# schematic-saved-reopened.net
KiCad netlist of a schematic drawn in EasyEDA
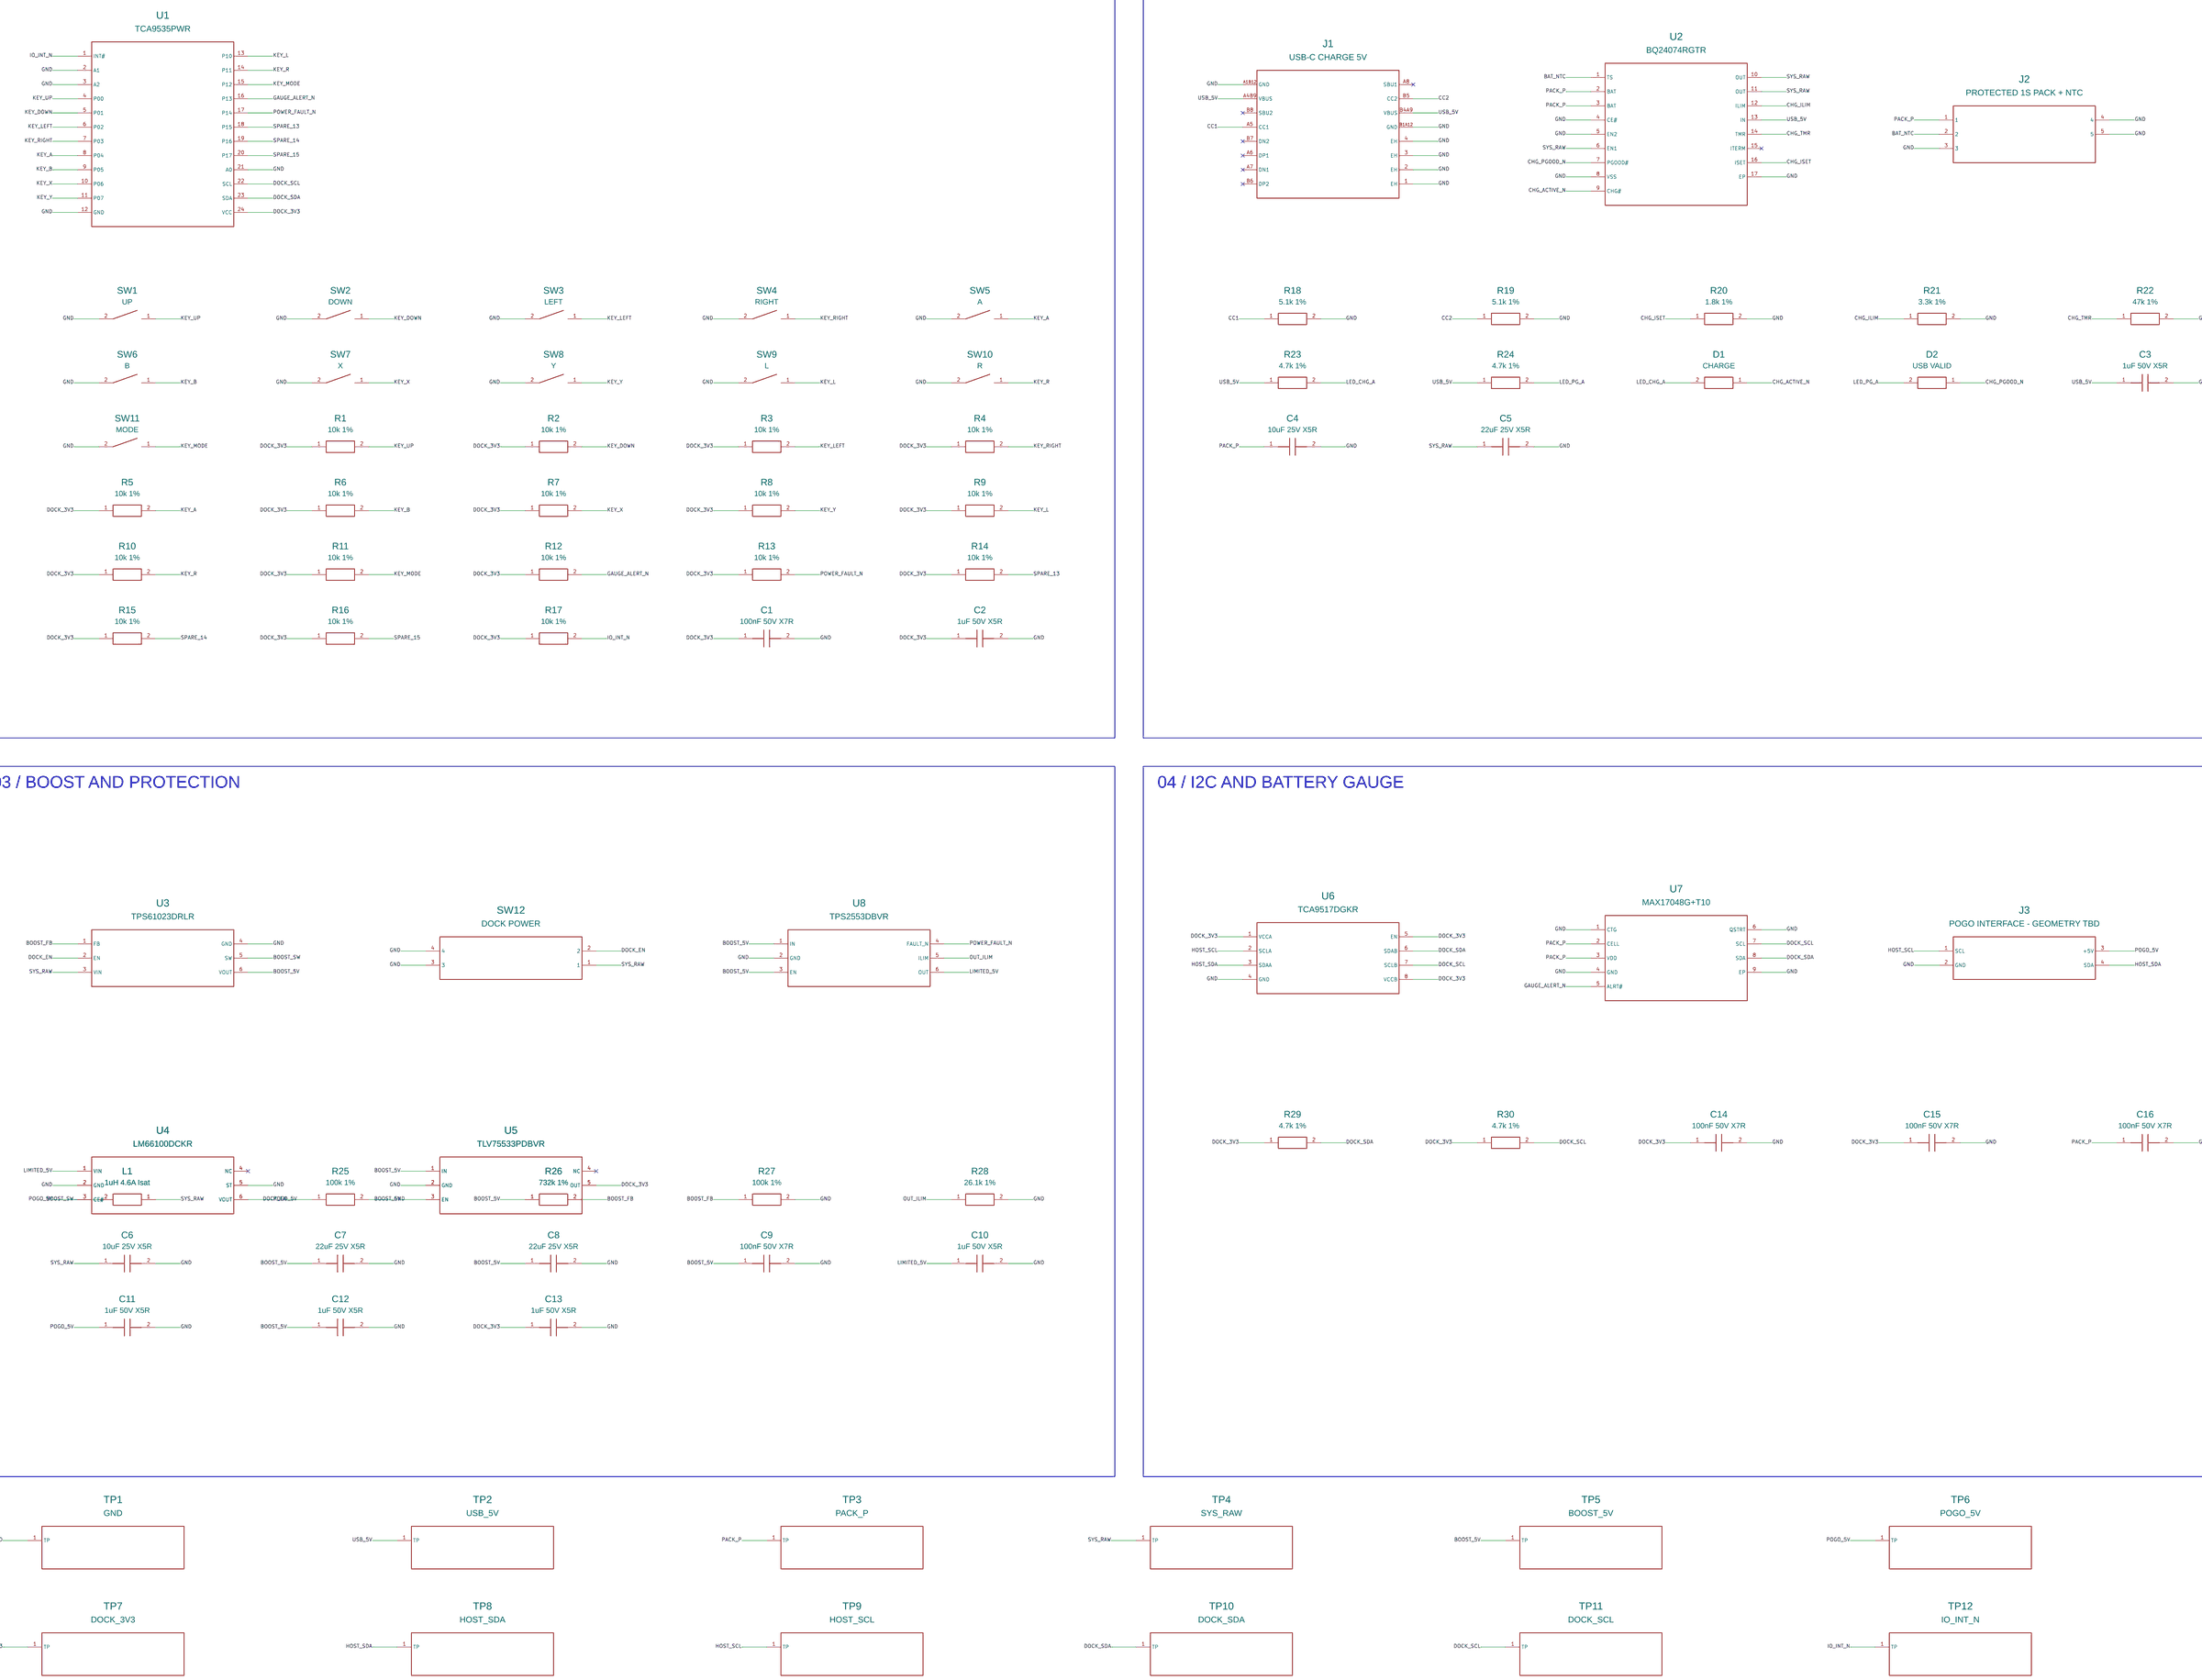
[diagram p0: schematic sheet]

(export (version "E")
  (design (tool "Eeschema 10.0.6"))
  (components
    (comp (ref "C1") (value "100nF 50V X7R") (libsource (lib "") (part "100nF 50V X7R")))
    (comp (ref "C2")
      (value "1uF 50V X5R")
      (fields
        (field (name "Manufacturer Part") "CL10A105KB8NNNC")
        (field (name "Manufacturer") "SAMSUNG(三星)")
      )
      (libsource (lib "") (part "1uF 50V X5R"))
    )
    (comp (ref "C3")
      (value "1uF 50V X5R")
      (fields
        (field (name "Manufacturer Part") "CL10A105KB8NNNC")
        (field (name "Manufacturer") "SAMSUNG(三星)")
      )
      (libsource (lib "") (part "1uF 50V X5R"))
    )
    (comp (ref "C4")
      (value "10uF 25V X5R")
      (fields
        (field (name "Manufacturer Part") "CL10A106MA8NRNC")
        (field (name "Manufacturer") "SAMSUNG(三星)")
      )
      (libsource (lib "") (part "10uF 25V X5R"))
    )
    (comp (ref "C5") (value "22uF 25V X5R") (libsource (lib "") (part "22uF 25V X5R")))
    (comp (ref "C6")
      (value "10uF 25V X5R")
      (fields
        (field (name "Manufacturer Part") "CL10A106MA8NRNC")
        (field (name "Manufacturer") "SAMSUNG(三星)")
      )
      (libsource (lib "") (part "10uF 25V X5R"))
    )
    (comp (ref "C7") (value "22uF 25V X5R") (libsource (lib "") (part "22uF 25V X5R")))
    (comp (ref "C8") (value "22uF 25V X5R") (libsource (lib "") (part "22uF 25V X5R")))
    (comp (ref "C9") (value "100nF 50V X7R") (libsource (lib "") (part "100nF 50V X7R")))
    (comp (ref "C10")
      (value "1uF 50V X5R")
      (fields
        (field (name "Manufacturer Part") "CL10A105KB8NNNC")
        (field (name "Manufacturer") "SAMSUNG(三星)")
      )
      (libsource (lib "") (part "1uF 50V X5R"))
    )
    (comp (ref "C11")
      (value "1uF 50V X5R")
      (fields
        (field (name "Manufacturer Part") "CL10A105KB8NNNC")
        (field (name "Manufacturer") "SAMSUNG(三星)")
      )
      (libsource (lib "") (part "1uF 50V X5R"))
    )
    (comp (ref "C12")
      (value "1uF 50V X5R")
      (fields
        (field (name "Manufacturer Part") "CL10A105KB8NNNC")
        (field (name "Manufacturer") "SAMSUNG(三星)")
      )
      (libsource (lib "") (part "1uF 50V X5R"))
    )
    (comp (ref "C13")
      (value "1uF 50V X5R")
      (fields
        (field (name "Manufacturer Part") "CL10A105KB8NNNC")
        (field (name "Manufacturer") "SAMSUNG(三星)")
      )
      (libsource (lib "") (part "1uF 50V X5R"))
    )
    (comp (ref "C14") (value "100nF 50V X7R") (libsource (lib "") (part "100nF 50V X7R")))
    (comp (ref "C15") (value "100nF 50V X7R") (libsource (lib "") (part "100nF 50V X7R")))
    (comp (ref "C16") (value "100nF 50V X7R") (libsource (lib "") (part "100nF 50V X7R")))
    (comp (ref "D1")
      (value "CHARGE")
      (fields (field (name "Manufacturer Part") "KT-0805黄灯") (field (name "Manufacturer") "KENTO"))
      (libsource (lib "") (part "CHARGE"))
    )
    (comp (ref "D2")
      (value "USB VALID")
      (fields (field (name "Manufacturer Part") "KT-0805黄灯") (field (name "Manufacturer") "KENTO"))
      (libsource (lib "") (part "USB VALID"))
    )
    (comp (ref "J1")
      (value "USB-C CHARGE 5V")
      (fields (field (name "Manufacturer Part") "TYPE-C-31-M-12") (field (name "Manufacturer") "韩国韩荣"))
      (libsource (lib "") (part "USB-C CHARGE 5V"))
    )
    (comp (ref "J2")
      (value "PROTECTED 1S PACK + NTC")
      (fields (field (name "Manufacturer Part") "B3B-PH-SM4-TB(LF)(SN)") (field (name "Manufacturer") "JST"))
      (libsource (lib "") (part "PROTECTED 1S PACK + NTC"))
    )
    (comp (ref "J3")
      (value "POGO INTERFACE - GEOMETRY TBD")
      (libsource (lib "") (part "POGO INTERFACE - GEOMETRY TBD"))
    )
    (comp (ref "L1")
      (value "1uH 4.6A Isat")
      (fields
        (field (name "Manufacturer Part") "FTC201610S1R0MBCA")
        (field (name "Manufacturer") "cjiang(长江微电)")
      )
      (libsource (lib "") (part "1uH 4.6A Isat"))
    )
    (comp (ref "R1")
      (value "10k 1%")
      (fields
        (field (name "Manufacturer Part") "0603WAF1002T5E")
        (field (name "Manufacturer") "UNI-ROYAL(厚声)")
      )
      (libsource (lib "") (part "10k 1%"))
    )
    (comp (ref "R2")
      (value "10k 1%")
      (fields
        (field (name "Manufacturer Part") "0603WAF1002T5E")
        (field (name "Manufacturer") "UNI-ROYAL(厚声)")
      )
      (libsource (lib "") (part "10k 1%"))
    )
    (comp (ref "R3")
      (value "10k 1%")
      (fields
        (field (name "Manufacturer Part") "0603WAF1002T5E")
        (field (name "Manufacturer") "UNI-ROYAL(厚声)")
      )
      (libsource (lib "") (part "10k 1%"))
    )
    (comp (ref "R4")
      (value "10k 1%")
      (fields
        (field (name "Manufacturer Part") "0603WAF1002T5E")
        (field (name "Manufacturer") "UNI-ROYAL(厚声)")
      )
      (libsource (lib "") (part "10k 1%"))
    )
    (comp (ref "R5")
      (value "10k 1%")
      (fields
        (field (name "Manufacturer Part") "0603WAF1002T5E")
        (field (name "Manufacturer") "UNI-ROYAL(厚声)")
      )
      (libsource (lib "") (part "10k 1%"))
    )
    (comp (ref "R6")
      (value "10k 1%")
      (fields
        (field (name "Manufacturer Part") "0603WAF1002T5E")
        (field (name "Manufacturer") "UNI-ROYAL(厚声)")
      )
      (libsource (lib "") (part "10k 1%"))
    )
    (comp (ref "R7")
      (value "10k 1%")
      (fields
        (field (name "Manufacturer Part") "0603WAF1002T5E")
        (field (name "Manufacturer") "UNI-ROYAL(厚声)")
      )
      (libsource (lib "") (part "10k 1%"))
    )
    (comp (ref "R8")
      (value "10k 1%")
      (fields
        (field (name "Manufacturer Part") "0603WAF1002T5E")
        (field (name "Manufacturer") "UNI-ROYAL(厚声)")
      )
      (libsource (lib "") (part "10k 1%"))
    )
    (comp (ref "R9")
      (value "10k 1%")
      (fields
        (field (name "Manufacturer Part") "0603WAF1002T5E")
        (field (name "Manufacturer") "UNI-ROYAL(厚声)")
      )
      (libsource (lib "") (part "10k 1%"))
    )
    (comp (ref "R10")
      (value "10k 1%")
      (fields
        (field (name "Manufacturer Part") "0603WAF1002T5E")
        (field (name "Manufacturer") "UNI-ROYAL(厚声)")
      )
      (libsource (lib "") (part "10k 1%"))
    )
    (comp (ref "R11")
      (value "10k 1%")
      (fields
        (field (name "Manufacturer Part") "0603WAF1002T5E")
        (field (name "Manufacturer") "UNI-ROYAL(厚声)")
      )
      (libsource (lib "") (part "10k 1%"))
    )
    (comp (ref "R12")
      (value "10k 1%")
      (fields
        (field (name "Manufacturer Part") "0603WAF1002T5E")
        (field (name "Manufacturer") "UNI-ROYAL(厚声)")
      )
      (libsource (lib "") (part "10k 1%"))
    )
    (comp (ref "R13")
      (value "10k 1%")
      (fields
        (field (name "Manufacturer Part") "0603WAF1002T5E")
        (field (name "Manufacturer") "UNI-ROYAL(厚声)")
      )
      (libsource (lib "") (part "10k 1%"))
    )
    (comp (ref "R14")
      (value "10k 1%")
      (fields
        (field (name "Manufacturer Part") "0603WAF1002T5E")
        (field (name "Manufacturer") "UNI-ROYAL(厚声)")
      )
      (libsource (lib "") (part "10k 1%"))
    )
    (comp (ref "R15")
      (value "10k 1%")
      (fields
        (field (name "Manufacturer Part") "0603WAF1002T5E")
        (field (name "Manufacturer") "UNI-ROYAL(厚声)")
      )
      (libsource (lib "") (part "10k 1%"))
    )
    (comp (ref "R16")
      (value "10k 1%")
      (fields
        (field (name "Manufacturer Part") "0603WAF1002T5E")
        (field (name "Manufacturer") "UNI-ROYAL(厚声)")
      )
      (libsource (lib "") (part "10k 1%"))
    )
    (comp (ref "R17")
      (value "10k 1%")
      (fields
        (field (name "Manufacturer Part") "0603WAF1002T5E")
        (field (name "Manufacturer") "UNI-ROYAL(厚声)")
      )
      (libsource (lib "") (part "10k 1%"))
    )
    (comp (ref "R18")
      (value "5.1k 1%")
      (fields
        (field (name "Manufacturer Part") "0603WAF5101T5E")
        (field (name "Manufacturer") "UNI-ROYAL(厚声)")
      )
      (libsource (lib "") (part "5.1k 1%"))
    )
    (comp (ref "R19")
      (value "5.1k 1%")
      (fields
        (field (name "Manufacturer Part") "0603WAF5101T5E")
        (field (name "Manufacturer") "UNI-ROYAL(厚声)")
      )
      (libsource (lib "") (part "5.1k 1%"))
    )
    (comp (ref "R20") (value "1.8k 1%") (libsource (lib "") (part "1.8k 1%")))
    (comp (ref "R21") (value "3.3k 1%") (libsource (lib "") (part "3.3k 1%")))
    (comp (ref "R22") (value "47k 1%") (libsource (lib "") (part "47k 1%")))
    (comp (ref "R23")
      (value "4.7k 1%")
      (fields
        (field (name "Manufacturer Part") "0603WAF4701T5E")
        (field (name "Manufacturer") "UNI-ROYAL(厚声)")
      )
      (libsource (lib "") (part "4.7k 1%"))
    )
    (comp (ref "R24")
      (value "4.7k 1%")
      (fields
        (field (name "Manufacturer Part") "0603WAF4701T5E")
        (field (name "Manufacturer") "UNI-ROYAL(厚声)")
      )
      (libsource (lib "") (part "4.7k 1%"))
    )
    (comp (ref "R25")
      (value "100k 1%")
      (fields
        (field (name "Manufacturer Part") "0603WAF1003T5E")
        (field (name "Manufacturer") "UNI-ROYAL(厚声)")
      )
      (libsource (lib "") (part "100k 1%"))
    )
    (comp (ref "R26") (value "732k 1%") (libsource (lib "") (part "732k 1%")))
    (comp (ref "R27")
      (value "100k 1%")
      (fields
        (field (name "Manufacturer Part") "0603WAF1003T5E")
        (field (name "Manufacturer") "UNI-ROYAL(厚声)")
      )
      (libsource (lib "") (part "100k 1%"))
    )
    (comp (ref "R28") (value "26.1k 1%") (libsource (lib "") (part "26.1k 1%")))
    (comp (ref "R29")
      (value "4.7k 1%")
      (fields
        (field (name "Manufacturer Part") "0603WAF4701T5E")
        (field (name "Manufacturer") "UNI-ROYAL(厚声)")
      )
      (libsource (lib "") (part "4.7k 1%"))
    )
    (comp (ref "R30")
      (value "4.7k 1%")
      (fields
        (field (name "Manufacturer Part") "0603WAF4701T5E")
        (field (name "Manufacturer") "UNI-ROYAL(厚声)")
      )
      (libsource (lib "") (part "4.7k 1%"))
    )
    (comp (ref "SW1")
      (value "UP")
      (fields (field (name "Manufacturer Part") "TS-1088-AR02016") (field (name "Manufacturer") "XUNPU(讯普)"))
      (libsource (lib "") (part "UP"))
    )
    (comp (ref "SW2")
      (value "DOWN")
      (fields (field (name "Manufacturer Part") "TS-1088-AR02016") (field (name "Manufacturer") "XUNPU(讯普)"))
      (libsource (lib "") (part "DOWN"))
    )
    (comp (ref "SW3")
      (value "LEFT")
      (fields (field (name "Manufacturer Part") "TS-1088-AR02016") (field (name "Manufacturer") "XUNPU(讯普)"))
      (libsource (lib "") (part "LEFT"))
    )
    (comp (ref "SW4")
      (value "RIGHT")
      (fields (field (name "Manufacturer Part") "TS-1088-AR02016") (field (name "Manufacturer") "XUNPU(讯普)"))
      (libsource (lib "") (part "RIGHT"))
    )
    (comp (ref "SW5")
      (value "A")
      (fields (field (name "Manufacturer Part") "TS-1088-AR02016") (field (name "Manufacturer") "XUNPU(讯普)"))
      (libsource (lib "") (part "A"))
    )
    (comp (ref "SW6")
      (value "B")
      (fields (field (name "Manufacturer Part") "TS-1088-AR02016") (field (name "Manufacturer") "XUNPU(讯普)"))
      (libsource (lib "") (part "B"))
    )
    (comp (ref "SW7")
      (value "X")
      (fields (field (name "Manufacturer Part") "TS-1088-AR02016") (field (name "Manufacturer") "XUNPU(讯普)"))
      (libsource (lib "") (part "X"))
    )
    (comp (ref "SW8")
      (value "Y")
      (fields (field (name "Manufacturer Part") "TS-1088-AR02016") (field (name "Manufacturer") "XUNPU(讯普)"))
      (libsource (lib "") (part "Y"))
    )
    (comp (ref "SW9")
      (value "L")
      (fields (field (name "Manufacturer Part") "TS-1088-AR02016") (field (name "Manufacturer") "XUNPU(讯普)"))
      (libsource (lib "") (part "L"))
    )
    (comp (ref "SW10")
      (value "R")
      (fields (field (name "Manufacturer Part") "TS-1088-AR02016") (field (name "Manufacturer") "XUNPU(讯普)"))
      (libsource (lib "") (part "R"))
    )
    (comp (ref "SW11")
      (value "MODE")
      (fields (field (name "Manufacturer Part") "TS-1088-AR02016") (field (name "Manufacturer") "XUNPU(讯普)"))
      (libsource (lib "") (part "MODE"))
    )
    (comp (ref "SW12")
      (value "DOCK POWER")
      (fields (field (name "Manufacturer Part") "MSK12C02") (field (name "Manufacturer") "SHOU HAN(首韩)"))
      (libsource (lib "") (part "DOCK POWER"))
    )
    (comp (ref "TP1") (value "GND") (libsource (lib "") (part "GND")))
    (comp (ref "TP2") (value "USB_5V") (libsource (lib "") (part "USB_5V")))
    (comp (ref "TP3") (value "PACK_P") (libsource (lib "") (part "PACK_P")))
    (comp (ref "TP4") (value "SYS_RAW") (libsource (lib "") (part "SYS_RAW")))
    (comp (ref "TP5") (value "BOOST_5V") (libsource (lib "") (part "BOOST_5V")))
    (comp (ref "TP6") (value "POGO_5V") (libsource (lib "") (part "POGO_5V")))
    (comp (ref "TP7") (value "DOCK_3V3") (libsource (lib "") (part "DOCK_3V3")))
    (comp (ref "TP8") (value "HOST_SDA") (libsource (lib "") (part "HOST_SDA")))
    (comp (ref "TP9") (value "HOST_SCL") (libsource (lib "") (part "HOST_SCL")))
    (comp (ref "TP10") (value "DOCK_SDA") (libsource (lib "") (part "DOCK_SDA")))
    (comp (ref "TP11") (value "DOCK_SCL") (libsource (lib "") (part "DOCK_SCL")))
    (comp (ref "TP12") (value "IO_INT_N") (libsource (lib "") (part "IO_INT_N")))
    (comp (ref "U1")
      (value "TCA9535PWR")
      (fields (field (name "Manufacturer") "TI(德州仪器)"))
      (libsource (lib "") (part "TCA9535PWR"))
    )
    (comp (ref "U2")
      (value "BQ24074RGTR")
      (fields (field (name "Manufacturer") "TI(德州仪器)"))
      (libsource (lib "") (part "BQ24074RGTR"))
    )
    (comp (ref "U3")
      (value "TPS61023DRLR")
      (fields (field (name "Manufacturer") "TI(德州仪器)"))
      (libsource (lib "") (part "TPS61023DRLR"))
    )
    (comp (ref "U4")
      (value "LM66100DCKR")
      (fields (field (name "Manufacturer") "TI(德州仪器)"))
      (libsource (lib "") (part "LM66100DCKR"))
    )
    (comp (ref "U5")
      (value "TLV75533PDBVR")
      (fields (field (name "Manufacturer") "TI(德州仪器)"))
      (libsource (lib "") (part "TLV75533PDBVR"))
    )
    (comp (ref "U6")
      (value "TCA9517DGKR")
      (fields (field (name "Manufacturer") "TI(德州仪器)"))
      (libsource (lib "") (part "TCA9517DGKR"))
    )
    (comp (ref "U7")
      (value "MAX17048G+T10")
      (fields (field (name "Manufacturer") "ADI(亚德诺)/MAXIM(美信)"))
      (libsource (lib "") (part "MAX17048G+T10"))
    )
    (comp (ref "U8") (value "TPS2553DBVR") (libsource (lib "") (part "TPS2553DBVR")))
  )
  (nets
    (net (code "1") (name "/BAT_NTC") (class "Default")
      (node (ref "J2") (pin "2") (pinfunction "2_2") (pintype "unspecified"))
      (node (ref "U2") (pin "1") (pinfunction "TS_1") (pintype "unspecified"))
    )
    (net (code "2") (name "/BOOST_5V") (class "Default")
      (node (ref "C12") (pin "1") (pintype "unspecified"))
      (node (ref "C7") (pin "1") (pintype "unspecified"))
      (node (ref "C8") (pin "1") (pintype "unspecified"))
      (node (ref "C9") (pin "1") (pintype "unspecified"))
      (node (ref "R26") (pin "1") (pintype "unspecified"))
      (node (ref "TP5") (pin "1") (pinfunction "TP_1") (pintype "unspecified"))
      (node (ref "U3") (pin "6") (pinfunction "VOUT_6") (pintype "unspecified"))
      (node (ref "U5") (pin "1") (pinfunction "IN_1") (pintype "unspecified"))
      (node (ref "U5") (pin "3") (pinfunction "EN_3") (pintype "unspecified"))
      (node (ref "U8") (pin "1") (pinfunction "IN_1") (pintype "unspecified"))
      (node (ref "U8") (pin "3") (pinfunction "EN_3") (pintype "unspecified"))
    )
    (net (code "3") (name "/BOOST_FB") (class "Default")
      (node (ref "R26") (pin "2") (pintype "unspecified"))
      (node (ref "R27") (pin "1") (pintype "unspecified"))
      (node (ref "U3") (pin "1") (pinfunction "FB_1") (pintype "unspecified"))
    )
    (net (code "4") (name "/BOOST_SW") (class "Default")
      (node (ref "C11") (pin "1") (pintype "unspecified"))
      (node (ref "J3") (pin "3") (pinfunction "+5V_3") (pintype "unspecified"))
      (node (ref "L1") (pin "2") (pintype "unspecified"))
      (node (ref "TP6") (pin "1") (pinfunction "TP_1") (pintype "unspecified"))
      (node (ref "U3") (pin "5") (pinfunction "SW_5") (pintype "unspecified"))
      (node (ref "U4") (pin "3") (pinfunction "CE#_3") (pintype "unspecified"))
      (node (ref "U4") (pin "6") (pinfunction "VOUT_6") (pintype "unspecified"))
    )
    (net (code "5") (name "/CC1") (class "Default")
      (node (ref "J1") (pin "A5") (pinfunction "CC1_A5") (pintype "unspecified"))
      (node (ref "R18") (pin "1") (pintype "unspecified"))
    )
    (net (code "6") (name "/CC2") (class "Default")
      (node (ref "J1") (pin "B5") (pinfunction "CC2_B5") (pintype "unspecified"))
      (node (ref "R19") (pin "1") (pintype "unspecified"))
    )
    (net (code "7") (name "/CHG_ACTIVE_N") (class "Default")
      (node (ref "D1") (pin "1") (pintype "unspecified"))
      (node (ref "U2") (pin "9") (pinfunction "CHG#_9") (pintype "unspecified"))
    )
    (net (code "8") (name "/CHG_ILIM") (class "Default")
      (node (ref "R21") (pin "1") (pintype "unspecified"))
      (node (ref "U2") (pin "12") (pinfunction "ILIM_12") (pintype "unspecified"))
    )
    (net (code "9") (name "/CHG_ISET") (class "Default")
      (node (ref "R20") (pin "1") (pintype "unspecified"))
      (node (ref "U2") (pin "16") (pinfunction "ISET_16") (pintype "unspecified"))
    )
    (net (code "10") (name "/CHG_PGOOD_N") (class "Default")
      (node (ref "D2") (pin "1") (pintype "unspecified"))
      (node (ref "U2") (pin "7") (pinfunction "PGOOD#_7") (pintype "unspecified"))
    )
    (net (code "11") (name "/CHG_TMR") (class "Default")
      (node (ref "R22") (pin "1") (pintype "unspecified"))
      (node (ref "U2") (pin "14") (pinfunction "TMR_14") (pintype "unspecified"))
    )
    (net (code "12") (name "/DOCK_3V3") (class "Default")
      (node (ref "C1") (pin "1") (pintype "unspecified"))
      (node (ref "C13") (pin "1") (pintype "unspecified"))
      (node (ref "C14") (pin "1") (pintype "unspecified"))
      (node (ref "C15") (pin "1") (pintype "unspecified"))
      (node (ref "C2") (pin "1") (pintype "unspecified"))
      (node (ref "R1") (pin "1") (pintype "unspecified"))
      (node (ref "R10") (pin "1") (pintype "unspecified"))
      (node (ref "R11") (pin "1") (pintype "unspecified"))
      (node (ref "R12") (pin "1") (pintype "unspecified"))
      (node (ref "R13") (pin "1") (pintype "unspecified"))
      (node (ref "R14") (pin "1") (pintype "unspecified"))
      (node (ref "R15") (pin "1") (pintype "unspecified"))
      (node (ref "R16") (pin "1") (pintype "unspecified"))
      (node (ref "R17") (pin "1") (pintype "unspecified"))
      (node (ref "R2") (pin "1") (pintype "unspecified"))
      (node (ref "R29") (pin "1") (pintype "unspecified"))
      (node (ref "R3") (pin "1") (pintype "unspecified"))
      (node (ref "R30") (pin "1") (pintype "unspecified"))
      (node (ref "R4") (pin "1") (pintype "unspecified"))
      (node (ref "R5") (pin "1") (pintype "unspecified"))
      (node (ref "R6") (pin "1") (pintype "unspecified"))
      (node (ref "R7") (pin "1") (pintype "unspecified"))
      (node (ref "R8") (pin "1") (pintype "unspecified"))
      (node (ref "R9") (pin "1") (pintype "unspecified"))
      (node (ref "TP7") (pin "1") (pinfunction "TP_1") (pintype "unspecified"))
      (node (ref "U1") (pin "24") (pinfunction "VCC_24") (pintype "unspecified"))
      (node (ref "U5") (pin "5") (pinfunction "OUT_5") (pintype "unspecified"))
      (node (ref "U6") (pin "1") (pinfunction "VCCA_1") (pintype "unspecified"))
      (node (ref "U6") (pin "5") (pinfunction "EN_5") (pintype "unspecified"))
      (node (ref "U6") (pin "8") (pinfunction "VCCB_8") (pintype "unspecified"))
    )
    (net (code "13") (name "/DOCK_EN") (class "Default")
      (node (ref "R25") (pin "1") (pintype "unspecified"))
      (node (ref "SW12") (pin "2") (pinfunction "2_2") (pintype "unspecified"))
      (node (ref "U3") (pin "2") (pinfunction "EN_2") (pintype "unspecified"))
    )
    (net (code "14") (name "/DOCK_SCL") (class "Default")
      (node (ref "R30") (pin "2") (pintype "unspecified"))
      (node (ref "TP11") (pin "1") (pinfunction "TP_1") (pintype "unspecified"))
      (node (ref "U1") (pin "22") (pinfunction "SCL_22") (pintype "unspecified"))
      (node (ref "U6") (pin "7") (pinfunction "SCLB_7") (pintype "unspecified"))
      (node (ref "U7") (pin "7") (pinfunction "SCL_7") (pintype "unspecified"))
    )
    (net (code "15") (name "/DOCK_SDA") (class "Default")
      (node (ref "R29") (pin "2") (pintype "unspecified"))
      (node (ref "TP10") (pin "1") (pinfunction "TP_1") (pintype "unspecified"))
      (node (ref "U1") (pin "23") (pinfunction "SDA_23") (pintype "unspecified"))
      (node (ref "U6") (pin "6") (pinfunction "SDAB_6") (pintype "unspecified"))
      (node (ref "U7") (pin "8") (pinfunction "SDA_8") (pintype "unspecified"))
    )
    (net (code "16") (name "/GAUGE_ALERT_N") (class "Default")
      (node (ref "R12") (pin "2") (pintype "unspecified"))
      (node (ref "U1") (pin "16") (pinfunction "P13_16") (pintype "unspecified"))
      (node (ref "U7") (pin "5") (pinfunction "ALRT#_5") (pintype "unspecified"))
    )
    (net (code "17") (name "/GND") (class "Default")
      (node (ref "C1") (pin "2") (pintype "unspecified"))
      (node (ref "C10") (pin "2") (pintype "unspecified"))
      (node (ref "C11") (pin "2") (pintype "unspecified"))
      (node (ref "C12") (pin "2") (pintype "unspecified"))
      (node (ref "C13") (pin "2") (pintype "unspecified"))
      (node (ref "C14") (pin "2") (pintype "unspecified"))
      (node (ref "C15") (pin "2") (pintype "unspecified"))
      (node (ref "C16") (pin "2") (pintype "unspecified"))
      (node (ref "C2") (pin "2") (pintype "unspecified"))
      (node (ref "C3") (pin "2") (pintype "unspecified"))
      (node (ref "C4") (pin "2") (pintype "unspecified"))
      (node (ref "C5") (pin "2") (pintype "unspecified"))
      (node (ref "C6") (pin "2") (pintype "unspecified"))
      (node (ref "C7") (pin "2") (pintype "unspecified"))
      (node (ref "C8") (pin "2") (pintype "unspecified"))
      (node (ref "C9") (pin "2") (pintype "unspecified"))
      (node (ref "J1") (pin "1") (pinfunction "EH_1") (pintype "unspecified"))
      (node (ref "J1") (pin "2") (pinfunction "EH_2") (pintype "unspecified"))
      (node (ref "J1") (pin "3") (pinfunction "EH_3") (pintype "unspecified"))
      (node (ref "J1") (pin "4") (pinfunction "EH_4") (pintype "unspecified"))
      (node (ref "J1") (pin "A1B12") (pinfunction "GND_A1B12") (pintype "unspecified"))
      (node (ref "J1") (pin "B1A12") (pinfunction "GND_B1A12") (pintype "unspecified"))
      (node (ref "J2") (pin "3") (pinfunction "3_3") (pintype "unspecified"))
      (node (ref "J2") (pin "4") (pinfunction "4_4") (pintype "unspecified"))
      (node (ref "J2") (pin "5") (pinfunction "5_5") (pintype "unspecified"))
      (node (ref "J3") (pin "2") (pinfunction "GND_2") (pintype "unspecified"))
      (node (ref "R18") (pin "2") (pintype "unspecified"))
      (node (ref "R19") (pin "2") (pintype "unspecified"))
      (node (ref "R20") (pin "2") (pintype "unspecified"))
      (node (ref "R21") (pin "2") (pintype "unspecified"))
      (node (ref "R22") (pin "2") (pintype "unspecified"))
      (node (ref "R25") (pin "2") (pintype "unspecified"))
      (node (ref "R27") (pin "2") (pintype "unspecified"))
      (node (ref "R28") (pin "2") (pintype "unspecified"))
      (node (ref "SW1") (pin "2") (pintype "unspecified"))
      (node (ref "SW10") (pin "2") (pintype "unspecified"))
      (node (ref "SW11") (pin "2") (pintype "unspecified"))
      (node (ref "SW12") (pin "3") (pinfunction "3_3") (pintype "unspecified"))
      (node (ref "SW12") (pin "4") (pinfunction "4_4") (pintype "unspecified"))
      (node (ref "SW2") (pin "2") (pintype "unspecified"))
      (node (ref "SW3") (pin "2") (pintype "unspecified"))
      (node (ref "SW4") (pin "2") (pintype "unspecified"))
      (node (ref "SW5") (pin "2") (pintype "unspecified"))
      (node (ref "SW6") (pin "2") (pintype "unspecified"))
      (node (ref "SW7") (pin "2") (pintype "unspecified"))
      (node (ref "SW8") (pin "2") (pintype "unspecified"))
      (node (ref "SW9") (pin "2") (pintype "unspecified"))
      (node (ref "TP1") (pin "1") (pinfunction "TP_1") (pintype "unspecified"))
      (node (ref "U1") (pin "12") (pinfunction "GND_12") (pintype "unspecified"))
      (node (ref "U1") (pin "2") (pinfunction "A1_2") (pintype "unspecified"))
      (node (ref "U1") (pin "21") (pinfunction "A0_21") (pintype "unspecified"))
      (node (ref "U1") (pin "3") (pinfunction "A2_3") (pintype "unspecified"))
      (node (ref "U2") (pin "17") (pinfunction "EP_17") (pintype "unspecified"))
      (node (ref "U2") (pin "4") (pinfunction "CE#_4") (pintype "unspecified"))
      (node (ref "U2") (pin "5") (pinfunction "EN2_5") (pintype "unspecified"))
      (node (ref "U2") (pin "8") (pinfunction "VSS_8") (pintype "unspecified"))
      (node (ref "U3") (pin "4") (pinfunction "GND_4") (pintype "unspecified"))
      (node (ref "U4") (pin "2") (pinfunction "GND_2") (pintype "unspecified"))
      (node (ref "U4") (pin "5") (pinfunction "ST_5") (pintype "unspecified"))
      (node (ref "U5") (pin "2") (pinfunction "GND_2") (pintype "unspecified"))
      (node (ref "U6") (pin "4") (pinfunction "GND_4") (pintype "unspecified"))
      (node (ref "U7") (pin "1") (pinfunction "CTG_1") (pintype "unspecified"))
      (node (ref "U7") (pin "4") (pinfunction "GND_4") (pintype "unspecified"))
      (node (ref "U7") (pin "6") (pinfunction "QSTRT_6") (pintype "unspecified"))
      (node (ref "U7") (pin "9") (pinfunction "EP_9") (pintype "unspecified"))
      (node (ref "U8") (pin "2") (pinfunction "GND_2") (pintype "unspecified"))
    )
    (net (code "18") (name "/HOST_SCL") (class "Default")
      (node (ref "J3") (pin "1") (pinfunction "SCL_1") (pintype "unspecified"))
      (node (ref "TP9") (pin "1") (pinfunction "TP_1") (pintype "unspecified"))
      (node (ref "U6") (pin "2") (pinfunction "SCLA_2") (pintype "unspecified"))
    )
    (net (code "19") (name "/HOST_SDA") (class "Default")
      (node (ref "J3") (pin "4") (pinfunction "SDA_4") (pintype "unspecified"))
      (node (ref "TP8") (pin "1") (pinfunction "TP_1") (pintype "unspecified"))
      (node (ref "U6") (pin "3") (pinfunction "SDAA_3") (pintype "unspecified"))
    )
    (net (code "20") (name "/IO_INT_N") (class "Default")
      (node (ref "R17") (pin "2") (pintype "unspecified"))
      (node (ref "TP12") (pin "1") (pinfunction "TP_1") (pintype "unspecified"))
      (node (ref "U1") (pin "1") (pinfunction "INT#_1") (pintype "unspecified"))
    )
    (net (code "21") (name "/KEY_A") (class "Default")
      (node (ref "R5") (pin "2") (pintype "unspecified"))
      (node (ref "SW5") (pin "1") (pintype "unspecified"))
      (node (ref "U1") (pin "8") (pinfunction "P04_8") (pintype "unspecified"))
    )
    (net (code "22") (name "/KEY_B") (class "Default")
      (node (ref "R6") (pin "2") (pintype "unspecified"))
      (node (ref "SW6") (pin "1") (pintype "unspecified"))
      (node (ref "U1") (pin "9") (pinfunction "P05_9") (pintype "unspecified"))
    )
    (net (code "23") (name "/KEY_DOWN") (class "Default")
      (node (ref "R2") (pin "2") (pintype "unspecified"))
      (node (ref "SW2") (pin "1") (pintype "unspecified"))
      (node (ref "U1") (pin "5") (pinfunction "P01_5") (pintype "unspecified"))
    )
    (net (code "24") (name "/KEY_L") (class "Default")
      (node (ref "R9") (pin "2") (pintype "unspecified"))
      (node (ref "SW9") (pin "1") (pintype "unspecified"))
      (node (ref "U1") (pin "13") (pinfunction "P10_13") (pintype "unspecified"))
    )
    (net (code "25") (name "/KEY_LEFT") (class "Default")
      (node (ref "R3") (pin "2") (pintype "unspecified"))
      (node (ref "SW3") (pin "1") (pintype "unspecified"))
      (node (ref "U1") (pin "6") (pinfunction "P02_6") (pintype "unspecified"))
    )
    (net (code "26") (name "/KEY_MODE") (class "Default")
      (node (ref "R11") (pin "2") (pintype "unspecified"))
      (node (ref "SW11") (pin "1") (pintype "unspecified"))
      (node (ref "U1") (pin "15") (pinfunction "P12_15") (pintype "unspecified"))
    )
    (net (code "27") (name "/KEY_R") (class "Default")
      (node (ref "R10") (pin "2") (pintype "unspecified"))
      (node (ref "SW10") (pin "1") (pintype "unspecified"))
      (node (ref "U1") (pin "14") (pinfunction "P11_14") (pintype "unspecified"))
    )
    (net (code "28") (name "/KEY_RIGHT") (class "Default")
      (node (ref "R4") (pin "2") (pintype "unspecified"))
      (node (ref "SW4") (pin "1") (pintype "unspecified"))
      (node (ref "U1") (pin "7") (pinfunction "P03_7") (pintype "unspecified"))
    )
    (net (code "29") (name "/KEY_UP") (class "Default")
      (node (ref "R1") (pin "2") (pintype "unspecified"))
      (node (ref "SW1") (pin "1") (pintype "unspecified"))
      (node (ref "U1") (pin "4") (pinfunction "P00_4") (pintype "unspecified"))
    )
    (net (code "30") (name "/KEY_X") (class "Default")
      (node (ref "R7") (pin "2") (pintype "unspecified"))
      (node (ref "SW7") (pin "1") (pintype "unspecified"))
      (node (ref "U1") (pin "10") (pinfunction "P06_10") (pintype "unspecified"))
    )
    (net (code "31") (name "/KEY_Y") (class "Default")
      (node (ref "R8") (pin "2") (pintype "unspecified"))
      (node (ref "SW8") (pin "1") (pintype "unspecified"))
      (node (ref "U1") (pin "11") (pinfunction "P07_11") (pintype "unspecified"))
    )
    (net (code "32") (name "/LED_CHG_A") (class "Default")
      (node (ref "D1") (pin "2") (pintype "unspecified"))
      (node (ref "R23") (pin "2") (pintype "unspecified"))
    )
    (net (code "33") (name "/LED_PG_A") (class "Default")
      (node (ref "D2") (pin "2") (pintype "unspecified"))
      (node (ref "R24") (pin "2") (pintype "unspecified"))
    )
    (net (code "34") (name "/LIMITED_5V") (class "Default")
      (node (ref "C10") (pin "1") (pintype "unspecified"))
      (node (ref "U4") (pin "1") (pinfunction "VIN_1") (pintype "unspecified"))
      (node (ref "U8") (pin "6") (pinfunction "OUT_6") (pintype "unspecified"))
    )
    (net (code "35") (name "/OUT_ILIM") (class "Default")
      (node (ref "R28") (pin "1") (pintype "unspecified"))
      (node (ref "U8") (pin "5") (pinfunction "ILIM_5") (pintype "unspecified"))
    )
    (net (code "36") (name "/PACK_P") (class "Default")
      (node (ref "C16") (pin "1") (pintype "unspecified"))
      (node (ref "C4") (pin "1") (pintype "unspecified"))
      (node (ref "J2") (pin "1") (pinfunction "1_1") (pintype "unspecified"))
      (node (ref "TP3") (pin "1") (pinfunction "TP_1") (pintype "unspecified"))
      (node (ref "U2") (pin "2") (pinfunction "BAT_2") (pintype "unspecified"))
      (node (ref "U2") (pin "3") (pinfunction "BAT_3") (pintype "unspecified"))
      (node (ref "U7") (pin "2") (pinfunction "CELL_2") (pintype "unspecified"))
      (node (ref "U7") (pin "3") (pinfunction "VDD_3") (pintype "unspecified"))
    )
    (net (code "37") (name "/POWER_FAULT_N") (class "Default")
      (node (ref "R13") (pin "2") (pintype "unspecified"))
      (node (ref "U1") (pin "17") (pinfunction "P14_17") (pintype "unspecified"))
      (node (ref "U8") (pin "4") (pinfunction "FAULT_N_4") (pintype "unspecified"))
    )
    (net (code "38") (name "/SPARE_13") (class "Default")
      (node (ref "R14") (pin "2") (pintype "unspecified"))
      (node (ref "U1") (pin "18") (pinfunction "P15_18") (pintype "unspecified"))
    )
    (net (code "39") (name "/SPARE_14") (class "Default")
      (node (ref "R15") (pin "2") (pintype "unspecified"))
      (node (ref "U1") (pin "19") (pinfunction "P16_19") (pintype "unspecified"))
    )
    (net (code "40") (name "/SPARE_15") (class "Default")
      (node (ref "R16") (pin "2") (pintype "unspecified"))
      (node (ref "U1") (pin "20") (pinfunction "P17_20") (pintype "unspecified"))
    )
    (net (code "41") (name "/SYS_RAW") (class "Default")
      (node (ref "C5") (pin "1") (pintype "unspecified"))
      (node (ref "C6") (pin "1") (pintype "unspecified"))
      (node (ref "L1") (pin "1") (pintype "unspecified"))
      (node (ref "SW12") (pin "1") (pinfunction "1_1") (pintype "unspecified"))
      (node (ref "TP4") (pin "1") (pinfunction "TP_1") (pintype "unspecified"))
      (node (ref "U2") (pin "10") (pinfunction "OUT_10") (pintype "unspecified"))
      (node (ref "U2") (pin "11") (pinfunction "OUT_11") (pintype "unspecified"))
      (node (ref "U2") (pin "6") (pinfunction "EN1_6") (pintype "unspecified"))
      (node (ref "U3") (pin "3") (pinfunction "VIN_3") (pintype "unspecified"))
    )
    (net (code "42") (name "/USB_5V") (class "Default")
      (node (ref "C3") (pin "1") (pintype "unspecified"))
      (node (ref "J1") (pin "A4B9") (pinfunction "VBUS_A4B9") (pintype "unspecified"))
      (node (ref "J1") (pin "B4A9") (pinfunction "VBUS_B4A9") (pintype "unspecified"))
      (node (ref "R23") (pin "1") (pintype "unspecified"))
      (node (ref "R24") (pin "1") (pintype "unspecified"))
      (node (ref "TP2") (pin "1") (pinfunction "TP_1") (pintype "unspecified"))
      (node (ref "U2") (pin "13") (pinfunction "IN_13") (pintype "unspecified"))
    )
    (net (code "43") (name "unconnected-(J1-DN1-PadA7)") (class "Default")
      (node (ref "J1") (pin "A7") (pinfunction "DN1_A7") (pintype "unspecified+no_connect"))
    )
    (net (code "44") (name "unconnected-(J1-DN2-PadB7)") (class "Default")
      (node (ref "J1") (pin "B7") (pinfunction "DN2_B7") (pintype "unspecified+no_connect"))
    )
    (net (code "45") (name "unconnected-(J1-DP1-PadA6)") (class "Default")
      (node (ref "J1") (pin "A6") (pinfunction "DP1_A6") (pintype "unspecified+no_connect"))
    )
    (net (code "46") (name "unconnected-(J1-DP2-PadB6)") (class "Default")
      (node (ref "J1") (pin "B6") (pinfunction "DP2_B6") (pintype "unspecified+no_connect"))
    )
    (net (code "47") (name "unconnected-(J1-SBU1-PadA8)") (class "Default")
      (node (ref "J1") (pin "A8") (pinfunction "SBU1_A8") (pintype "unspecified+no_connect"))
    )
    (net (code "48") (name "unconnected-(J1-SBU2-PadB8)") (class "Default")
      (node (ref "J1") (pin "B8") (pinfunction "SBU2_B8") (pintype "unspecified+no_connect"))
    )
    (net (code "49") (name "unconnected-(U2-ITERM-Pad15)") (class "Default")
      (node (ref "U2") (pin "15") (pinfunction "ITERM_15") (pintype "unspecified+no_connect"))
    )
    (net (code "50") (name "unconnected-(U4-NC-Pad4)") (class "Default")
      (node (ref "U4") (pin "4") (pinfunction "NC_4") (pintype "unspecified+no_connect"))
    )
    (net (code "51") (name "unconnected-(U5-NC-Pad4)") (class "Default")
      (node (ref "U5") (pin "4") (pinfunction "NC_4") (pintype "unspecified+no_connect"))
    )
  )
)
